# BearJR.net
KiCad netlist of a schematic drawn in EAGLE
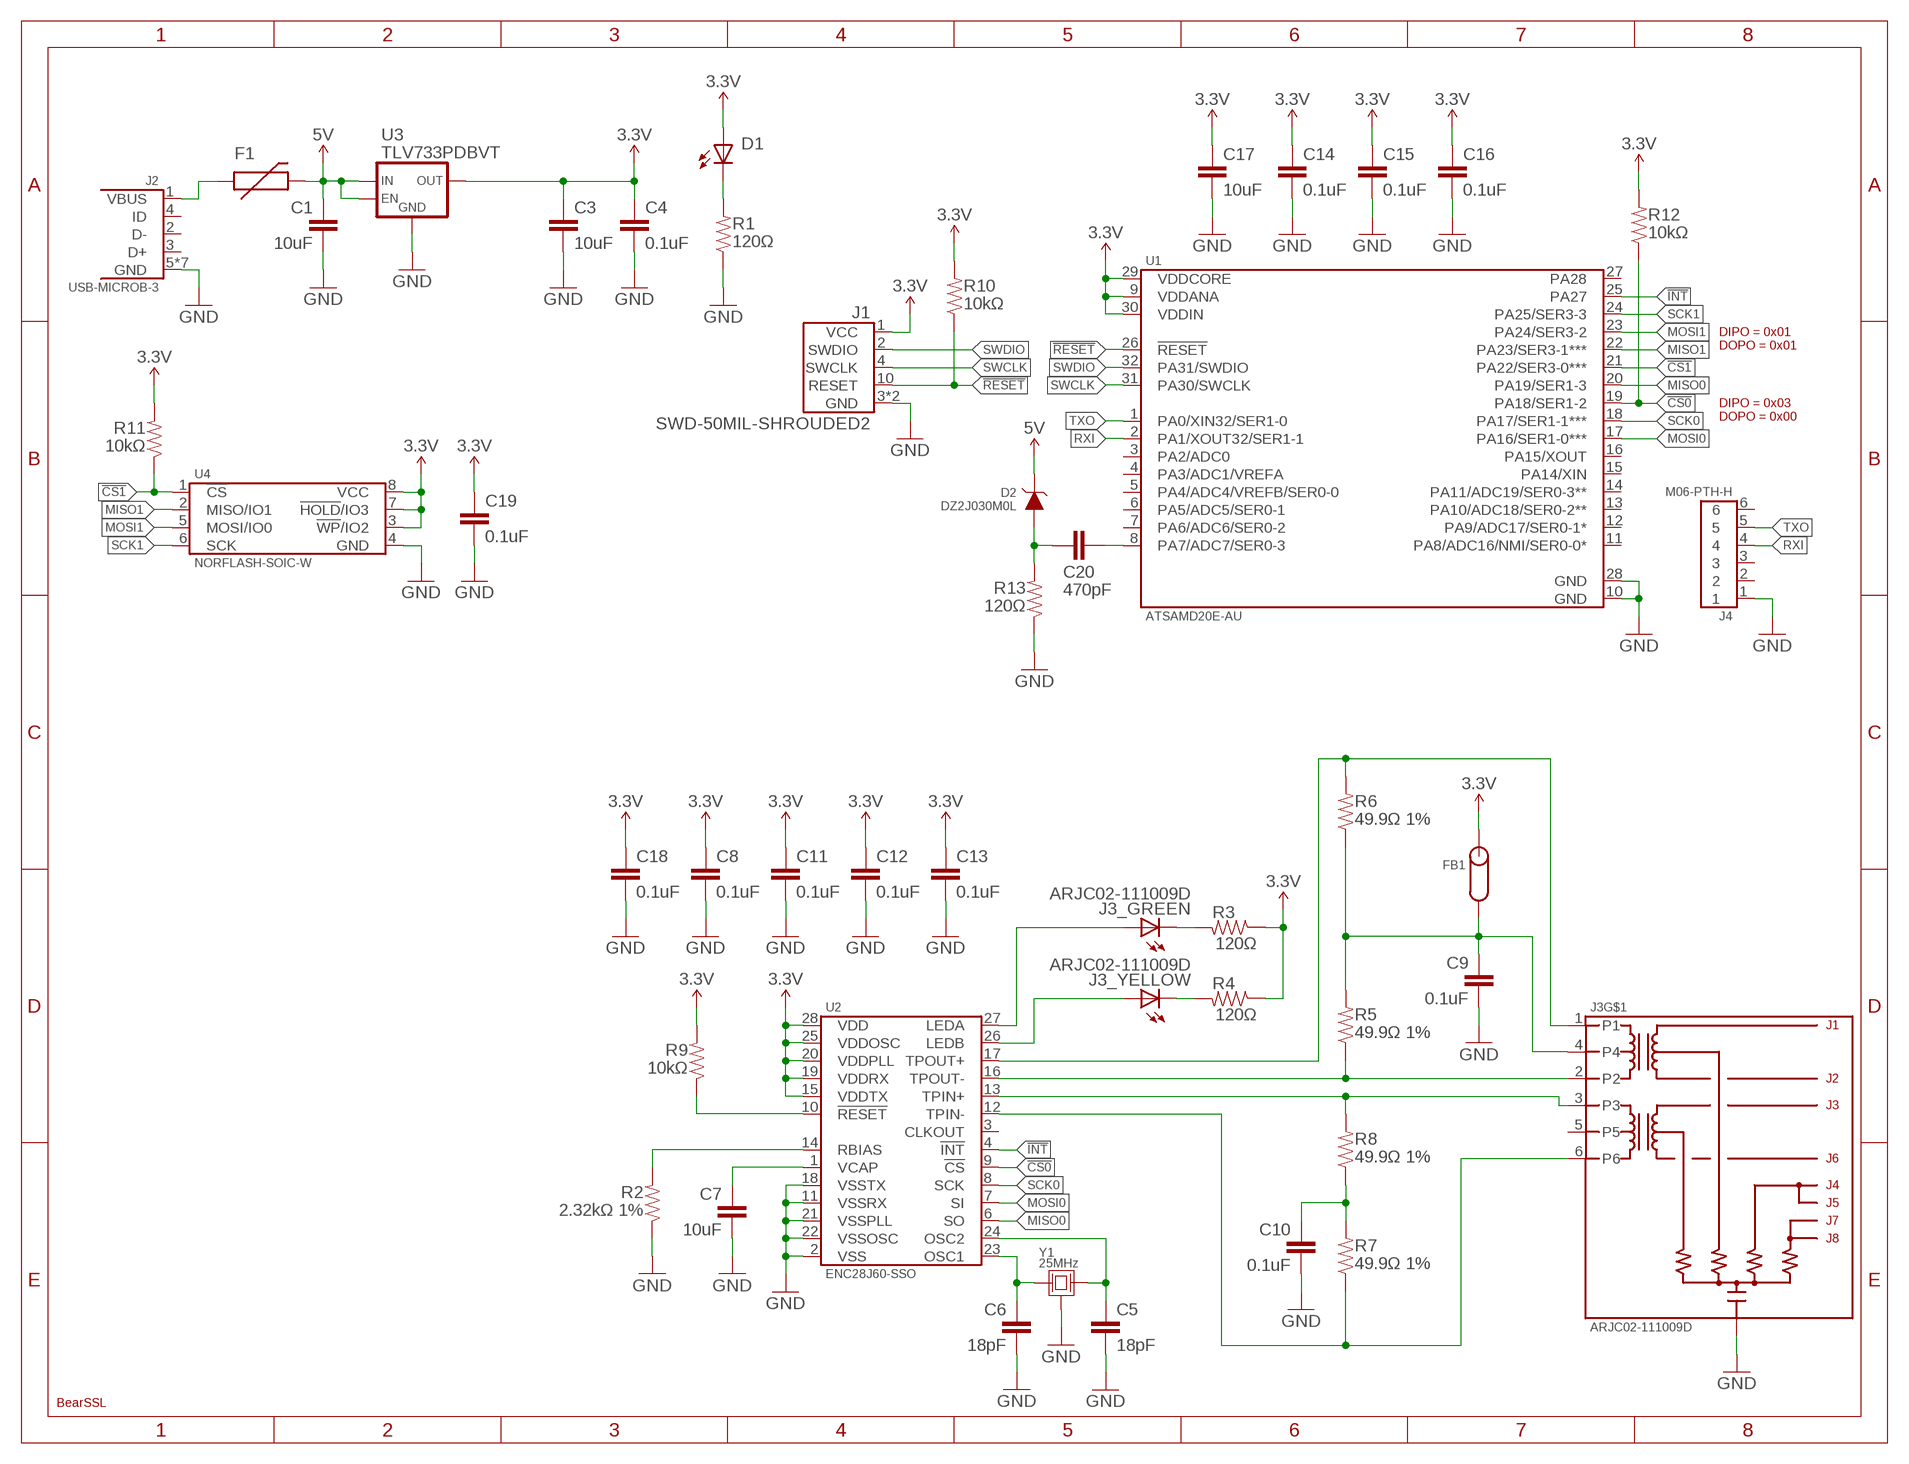
[diagram p0: schematic, sheet 1]

(export (version "E")
  (design (tool "Eeschema 10.0.6"))
  (components
    (comp (ref "C1")
      (value "10uF")
      (footprint "eagle-import:0603-CAP")
      (libsource (lib "eagle-import") (part "CAP-0603"))
    )
    (comp (ref "C3")
      (value "10uF")
      (footprint "eagle-import:0603-CAP")
      (libsource (lib "eagle-import") (part "CAP-0603"))
    )
    (comp (ref "C4")
      (value "0.1uF")
      (footprint "eagle-import:0603-CAP")
      (libsource (lib "eagle-import") (part "CAP-0603"))
    )
    (comp (ref "C5")
      (value "18pF")
      (footprint "eagle-import:0603-CAP")
      (libsource (lib "eagle-import") (part "CAP-0603"))
    )
    (comp (ref "C6")
      (value "18pF")
      (footprint "eagle-import:0603-CAP")
      (libsource (lib "eagle-import") (part "CAP-0603"))
    )
    (comp (ref "C7")
      (value "10uF")
      (footprint "eagle-import:0603-CAP")
      (libsource (lib "eagle-import") (part "CAP-0603"))
    )
    (comp (ref "C8")
      (value "0.1uF")
      (footprint "eagle-import:0603-CAP")
      (libsource (lib "eagle-import") (part "CAP-0603"))
    )
    (comp (ref "C9")
      (value "0.1uF")
      (footprint "eagle-import:0603-CAP")
      (libsource (lib "eagle-import") (part "CAP-0603"))
    )
    (comp (ref "C10")
      (value "0.1uF")
      (footprint "eagle-import:0603-CAP")
      (libsource (lib "eagle-import") (part "CAP-0603"))
    )
    (comp (ref "C11")
      (value "0.1uF")
      (footprint "eagle-import:0603-CAP")
      (libsource (lib "eagle-import") (part "CAP-0603"))
    )
    (comp (ref "C12")
      (value "0.1uF")
      (footprint "eagle-import:0603-CAP")
      (libsource (lib "eagle-import") (part "CAP-0603"))
    )
    (comp (ref "C13")
      (value "0.1uF")
      (footprint "eagle-import:0603-CAP")
      (libsource (lib "eagle-import") (part "CAP-0603"))
    )
    (comp (ref "C14")
      (value "0.1uF")
      (footprint "eagle-import:0603-CAP")
      (libsource (lib "eagle-import") (part "CAP-0603"))
    )
    (comp (ref "C15")
      (value "0.1uF")
      (footprint "eagle-import:0603-CAP")
      (libsource (lib "eagle-import") (part "CAP-0603"))
    )
    (comp (ref "C16")
      (value "0.1uF")
      (footprint "eagle-import:0603-CAP")
      (libsource (lib "eagle-import") (part "CAP-0603"))
    )
    (comp (ref "C17")
      (value "10uF")
      (footprint "eagle-import:0603-CAP")
      (libsource (lib "eagle-import") (part "CAP-0603"))
    )
    (comp (ref "C18")
      (value "0.1uF")
      (footprint "eagle-import:0603-CAP")
      (libsource (lib "eagle-import") (part "CAP-0603"))
    )
    (comp (ref "C19")
      (value "0.1uF")
      (footprint "eagle-import:0603-CAP")
      (libsource (lib "eagle-import") (part "CAP-0603"))
    )
    (comp (ref "C20")
      (value "470pF")
      (footprint "eagle-import:0603-CAP")
      (libsource (lib "eagle-import") (part "CAP-0603"))
    )
    (comp (ref "D1")
      (value "LED-0603")
      (footprint "eagle-import:0603-LED")
      (libsource (lib "eagle-import") (part "LED-0603"))
    )
    (comp (ref "D2")
      (value "DZ2J030M0L")
      (footprint "eagle-import:SC-90")
      (libsource (lib "eagle-import") (part "ZENER-SC90"))
    )
    (comp (ref "F1")
      (value "PTC-1206")
      (footprint "eagle-import:1206-PTC")
      (libsource (lib "eagle-import") (part "PTC-1206"))
    )
    (comp (ref "FB1")
      (value "FERRITE-0805")
      (footprint "eagle-import:0805")
      (libsource (lib "eagle-import") (part "FERRITE-0805"))
    )
    (comp (ref "J1")
      (value "SWD-50MIL-SHROUDED2")
      (footprint "eagle-import:M05X2-50MIL-SHROUD")
      (libsource (lib "eagle-import") (part "SWD-50MIL-SHROUDED2"))
    )
    (comp (ref "J2")
      (value "USB-MICROB-3")
      (footprint "eagle-import:10118192-0001LF")
      (libsource (lib "eagle-import") (part "USB-MICROB-3"))
    )
    (comp (ref "J3")
      (value "ARJC02-111009D")
      (footprint "eagle-import:ETHERNET")
      (libsource (lib "eagle-import") (part "ARJC02-111009D"))
    )
    (comp (ref "J4")
      (value "M06-PTH-H")
      (footprint "eagle-import:M06-PTH-H")
      (libsource (lib "eagle-import") (part "M06-PTH-H"))
    )
    (comp (ref "R1")
      (value "120Ω")
      (footprint "eagle-import:0603-CAP")
      (libsource (lib "eagle-import") (part "RESISTOR-0603"))
    )
    (comp (ref "R2")
      (value "2.32kΩ 1%")
      (footprint "eagle-import:0603-CAP")
      (libsource (lib "eagle-import") (part "RESISTOR-0603"))
    )
    (comp (ref "R3")
      (value "120Ω")
      (footprint "eagle-import:0603-CAP")
      (libsource (lib "eagle-import") (part "RESISTOR-0603"))
    )
    (comp (ref "R4")
      (value "120Ω")
      (footprint "eagle-import:0603-CAP")
      (libsource (lib "eagle-import") (part "RESISTOR-0603"))
    )
    (comp (ref "R5")
      (value "49.9Ω 1%")
      (footprint "eagle-import:0805-RES")
      (libsource (lib "eagle-import") (part "RESISTOR-0805"))
    )
    (comp (ref "R6")
      (value "49.9Ω 1%")
      (footprint "eagle-import:0805-RES")
      (libsource (lib "eagle-import") (part "RESISTOR-0805"))
    )
    (comp (ref "R7")
      (value "49.9Ω 1%")
      (footprint "eagle-import:0805-RES")
      (libsource (lib "eagle-import") (part "RESISTOR-0805"))
    )
    (comp (ref "R8")
      (value "49.9Ω 1%")
      (footprint "eagle-import:0805-RES")
      (libsource (lib "eagle-import") (part "RESISTOR-0805"))
    )
    (comp (ref "R9")
      (value "10kΩ")
      (footprint "eagle-import:0603-CAP")
      (libsource (lib "eagle-import") (part "RESISTOR-0603"))
    )
    (comp (ref "R10")
      (value "10kΩ")
      (footprint "eagle-import:0603-CAP")
      (libsource (lib "eagle-import") (part "RESISTOR-0603"))
    )
    (comp (ref "R11")
      (value "10kΩ")
      (footprint "eagle-import:0603-CAP")
      (libsource (lib "eagle-import") (part "RESISTOR-0603"))
    )
    (comp (ref "R12")
      (value "10kΩ")
      (footprint "eagle-import:0603-CAP")
      (libsource (lib "eagle-import") (part "RESISTOR-0603"))
    )
    (comp (ref "R13")
      (value "120Ω")
      (footprint "eagle-import:0603-CAP")
      (libsource (lib "eagle-import") (part "RESISTOR-0603"))
    )
    (comp (ref "U$1")
      (value "BEAR_SSL")
      (footprint "eagle-import:BEAR_SSL")
      (libsource (lib "eagle-import") (part "BEAR_SSL"))
    )
    (comp (ref "U1")
      (value "ATSAMD20E-AU")
      (footprint "eagle-import:TQFP-32")
      (libsource (lib "eagle-import") (part "ATSAMD20E-AU"))
    )
    (comp (ref "U2")
      (value "ENC28J60-SSO")
      (footprint "eagle-import:SSOP-28")
      (libsource (lib "eagle-import") (part "ENC28J60-SSO"))
    )
    (comp (ref "U3")
      (value "TLV733PDBVT")
      (footprint "eagle-import:SOT-23-5")
      (libsource (lib "eagle-import") (part "TLV733PDBVT"))
    )
    (comp (ref "U4")
      (value "NORFLASH-SOIC-W")
      (footprint "eagle-import:SOIC-8-W")
      (libsource (lib "eagle-import") (part "NORFLASH-SOIC-W"))
    )
    (comp (ref "Y1")
      (value "25MHz")
      (footprint "eagle-import:FA-238")
      (libsource (lib "eagle-import") (part "CRYSTAL-3.2X2.5"))
    )
  )
  (nets
    (net (code "1") (name "/~{CS0}") (class "Default")
      (node (ref "R12") (pin "1") (pinfunction "1_1") (pintype "passive"))
      (node (ref "U1") (pin "19") (pinfunction "PA18/SER1-2_19") (pintype "bidirectional"))
      (node (ref "U2") (pin "9") (pinfunction "~{CS}_9") (pintype "bidirectional"))
    )
    (net (code "2") (name "/~{CS1}") (class "Default")
      (node (ref "R11") (pin "1") (pinfunction "1_1") (pintype "passive"))
      (node (ref "U1") (pin "21") (pinfunction "PA22/SER3-0***_21") (pintype "bidirectional"))
      (node (ref "U4") (pin "1") (pinfunction "~{CS}_1") (pintype "bidirectional"))
    )
    (net (code "3") (name "/~{INT}") (class "Default")
      (node (ref "U1") (pin "25") (pinfunction "PA27_25") (pintype "bidirectional"))
      (node (ref "U2") (pin "4") (pinfunction "~{INT}_4") (pintype "bidirectional"))
    )
    (net (code "4") (name "/~{RESET}") (class "Default")
      (node (ref "J1") (pin "10") (pinfunction "RESET_10") (pintype "bidirectional"))
      (node (ref "R10") (pin "1") (pinfunction "1_1") (pintype "passive"))
      (node (ref "U1") (pin "26") (pinfunction "~{RESET}_26") (pintype "bidirectional"))
    )
    (net (code "5") (name "3.3V") (class "Default")
      (node (ref "C11") (pin "1") (pinfunction "1_1") (pintype "passive"))
      (node (ref "C12") (pin "1") (pinfunction "1_1") (pintype "passive"))
      (node (ref "C13") (pin "1") (pinfunction "1_1") (pintype "passive"))
      (node (ref "C14") (pin "1") (pinfunction "1_1") (pintype "passive"))
      (node (ref "C15") (pin "1") (pinfunction "1_1") (pintype "passive"))
      (node (ref "C16") (pin "1") (pinfunction "1_1") (pintype "passive"))
      (node (ref "C17") (pin "1") (pinfunction "1_1") (pintype "passive"))
      (node (ref "C18") (pin "1") (pinfunction "1_1") (pintype "passive"))
      (node (ref "C19") (pin "1") (pinfunction "1_1") (pintype "passive"))
      (node (ref "C3") (pin "1") (pinfunction "1_1") (pintype "passive"))
      (node (ref "C4") (pin "1") (pinfunction "1_1") (pintype "passive"))
      (node (ref "C8") (pin "1") (pinfunction "1_1") (pintype "passive"))
      (node (ref "D1") (pin "A") (pinfunction "A_A") (pintype "passive"))
      (node (ref "FB1") (pin "2") (pinfunction "P$2_2") (pintype "bidirectional"))
      (node (ref "J1") (pin "1") (pinfunction "VCC_1") (pintype "bidirectional"))
      (node (ref "R10") (pin "2") (pinfunction "2_2") (pintype "passive"))
      (node (ref "R11") (pin "2") (pinfunction "2_2") (pintype "passive"))
      (node (ref "R12") (pin "2") (pinfunction "2_2") (pintype "passive"))
      (node (ref "R3") (pin "1") (pinfunction "1_1") (pintype "passive"))
      (node (ref "R4") (pin "1") (pinfunction "1_1") (pintype "passive"))
      (node (ref "R9") (pin "2") (pinfunction "2_2") (pintype "passive"))
      (node (ref "U1") (pin "29") (pinfunction "VDDCORE_29") (pintype "bidirectional"))
      (node (ref "U1") (pin "30") (pinfunction "VDDIN_30") (pintype "bidirectional"))
      (node (ref "U1") (pin "9") (pinfunction "VDDANA_9") (pintype "bidirectional"))
      (node (ref "U2") (pin "15") (pinfunction "VDDTX_15") (pintype "bidirectional"))
      (node (ref "U2") (pin "19") (pinfunction "VDDRX_19") (pintype "bidirectional"))
      (node (ref "U2") (pin "20") (pinfunction "VDDPLL_20") (pintype "bidirectional"))
      (node (ref "U2") (pin "25") (pinfunction "VDDOSC_25") (pintype "bidirectional"))
      (node (ref "U2") (pin "28") (pinfunction "VDD_28") (pintype "bidirectional"))
      (node (ref "U3") (pin "5") (pinfunction "OUT_5") (pintype "output"))
      (node (ref "U4") (pin "3") (pinfunction "~{WP}/IO2_3") (pintype "bidirectional"))
      (node (ref "U4") (pin "7") (pinfunction "~{HOLD}/IO3_7") (pintype "bidirectional"))
      (node (ref "U4") (pin "8") (pinfunction "VCC_8") (pintype "bidirectional"))
    )
    (net (code "6") (name "5V") (class "Default")
      (node (ref "C1") (pin "1") (pinfunction "1_1") (pintype "passive"))
      (node (ref "D2") (pin "C") (pinfunction "C_C") (pintype "bidirectional"))
      (node (ref "F1") (pin "P$2") (pinfunction "2_P$2") (pintype "bidirectional"))
      (node (ref "U3") (pin "1") (pinfunction "IN_1") (pintype "input"))
      (node (ref "U3") (pin "3") (pinfunction "EN_3") (pintype "input"))
    )
    (net (code "7") (name "GND") (class "Default")
      (node (ref "C1") (pin "2") (pinfunction "2_2") (pintype "passive"))
      (node (ref "C10") (pin "2") (pinfunction "2_2") (pintype "passive"))
      (node (ref "C11") (pin "2") (pinfunction "2_2") (pintype "passive"))
      (node (ref "C12") (pin "2") (pinfunction "2_2") (pintype "passive"))
      (node (ref "C13") (pin "2") (pinfunction "2_2") (pintype "passive"))
      (node (ref "C14") (pin "2") (pinfunction "2_2") (pintype "passive"))
      (node (ref "C15") (pin "2") (pinfunction "2_2") (pintype "passive"))
      (node (ref "C16") (pin "2") (pinfunction "2_2") (pintype "passive"))
      (node (ref "C17") (pin "2") (pinfunction "2_2") (pintype "passive"))
      (node (ref "C18") (pin "2") (pinfunction "2_2") (pintype "passive"))
      (node (ref "C19") (pin "2") (pinfunction "2_2") (pintype "passive"))
      (node (ref "C3") (pin "2") (pinfunction "2_2") (pintype "passive"))
      (node (ref "C4") (pin "2") (pinfunction "2_2") (pintype "passive"))
      (node (ref "C5") (pin "2") (pinfunction "2_2") (pintype "passive"))
      (node (ref "C6") (pin "2") (pinfunction "2_2") (pintype "passive"))
      (node (ref "C7") (pin "2") (pinfunction "2_2") (pintype "passive"))
      (node (ref "C8") (pin "2") (pinfunction "2_2") (pintype "passive"))
      (node (ref "C9") (pin "2") (pinfunction "2_2") (pintype "passive"))
      (node (ref "J1") (pin "3") (pinfunction "GND_3") (pintype "bidirectional"))
      (node (ref "J1") (pin "5") (pinfunction "GND_5") (pintype "bidirectional"))
      (node (ref "J2") (pin "5") (pinfunction "GND_5") (pintype "bidirectional"))
      (node (ref "J2") (pin "P$10") (pinfunction "GND_P$10") (pintype "bidirectional"))
      (node (ref "J2") (pin "P$11") (pinfunction "GND_P$11") (pintype "bidirectional"))
      (node (ref "J2") (pin "P$6") (pinfunction "GND_P$6") (pintype "bidirectional"))
      (node (ref "J2") (pin "P$7") (pinfunction "GND_P$7") (pintype "bidirectional"))
      (node (ref "J2") (pin "P$8") (pinfunction "GND_P$8") (pintype "bidirectional"))
      (node (ref "J2") (pin "P$9") (pinfunction "GND_P$9") (pintype "bidirectional"))
      (node (ref "J3") (pin "8") (pinfunction "P8_8") (pintype "bidirectional"))
      (node (ref "J3") (pin "P$5") (pinfunction "P8_P$5") (pintype "bidirectional"))
      (node (ref "J3") (pin "P$6") (pinfunction "P8_P$6") (pintype "bidirectional"))
      (node (ref "J4") (pin "1") (pinfunction "1_1") (pintype "bidirectional"))
      (node (ref "R1") (pin "1") (pinfunction "1_1") (pintype "passive"))
      (node (ref "R13") (pin "1") (pinfunction "1_1") (pintype "passive"))
      (node (ref "R2") (pin "1") (pinfunction "1_1") (pintype "passive"))
      (node (ref "U1") (pin "10") (pinfunction "GND_10") (pintype "bidirectional"))
      (node (ref "U1") (pin "28") (pinfunction "GND_28") (pintype "bidirectional"))
      (node (ref "U2") (pin "11") (pinfunction "VSSRX_11") (pintype "bidirectional"))
      (node (ref "U2") (pin "18") (pinfunction "VSSTX_18") (pintype "bidirectional"))
      (node (ref "U2") (pin "2") (pinfunction "VSS_2") (pintype "bidirectional"))
      (node (ref "U2") (pin "21") (pinfunction "VSSPLL_21") (pintype "bidirectional"))
      (node (ref "U2") (pin "22") (pinfunction "VSSOSC_22") (pintype "bidirectional"))
      (node (ref "U3") (pin "2") (pinfunction "GND_2") (pintype "input"))
      (node (ref "U4") (pin "4") (pinfunction "GND_4") (pintype "bidirectional"))
      (node (ref "Y1") (pin "2") (pinfunction "GND_2") (pintype "bidirectional"))
      (node (ref "Y1") (pin "4") (pinfunction "GND_4") (pintype "bidirectional"))
    )
    (net (code "8") (name "MISO0") (class "Default")
      (node (ref "U1") (pin "20") (pinfunction "PA19/SER1-3_20") (pintype "bidirectional"))
      (node (ref "U2") (pin "6") (pinfunction "SO_6") (pintype "bidirectional"))
    )
    (net (code "9") (name "MISO1") (class "Default")
      (node (ref "U1") (pin "22") (pinfunction "PA23/SER3-1***_22") (pintype "bidirectional"))
      (node (ref "U4") (pin "2") (pinfunction "MISO/IO1_2") (pintype "bidirectional"))
    )
    (net (code "10") (name "MOSI0") (class "Default")
      (node (ref "U1") (pin "17") (pinfunction "PA16/SER1-0***_17") (pintype "bidirectional"))
      (node (ref "U2") (pin "7") (pinfunction "SI_7") (pintype "bidirectional"))
    )
    (net (code "11") (name "MOSI1") (class "Default")
      (node (ref "U1") (pin "23") (pinfunction "PA24/SER3-2_23") (pintype "bidirectional"))
      (node (ref "U4") (pin "5") (pinfunction "MOSI/IO0_5") (pintype "bidirectional"))
    )
    (net (code "12") (name "Net-(C10-Pad1)") (class "Default")
      (node (ref "C10") (pin "1") (pinfunction "1_1") (pintype "passive"))
      (node (ref "R7") (pin "2") (pinfunction "2_2") (pintype "passive"))
      (node (ref "R8") (pin "1") (pinfunction "1_1") (pintype "passive"))
    )
    (net (code "13") (name "Net-(C20-Pad1)") (class "Default")
      (node (ref "C20") (pin "1") (pinfunction "1_1") (pintype "passive"))
      (node (ref "D2") (pin "A") (pinfunction "A_A") (pintype "bidirectional"))
      (node (ref "R13") (pin "2") (pinfunction "2_2") (pintype "passive"))
    )
    (net (code "14") (name "Net-(D1-PadC)") (class "Default")
      (node (ref "D1") (pin "C") (pinfunction "C_C") (pintype "passive"))
      (node (ref "R1") (pin "2") (pinfunction "2_2") (pintype "passive"))
    )
    (net (code "15") (name "Net-(F1-1)") (class "Default")
      (node (ref "F1") (pin "P$1") (pinfunction "1_P$1") (pintype "bidirectional"))
      (node (ref "J2") (pin "1") (pinfunction "VBUS_1") (pintype "bidirectional"))
    )
    (net (code "16") (name "Net-(FB1-P$1)") (class "Default")
      (node (ref "C9") (pin "1") (pinfunction "1_1") (pintype "passive"))
      (node (ref "FB1") (pin "1") (pinfunction "P$1_1") (pintype "bidirectional"))
      (node (ref "J3") (pin "4") (pinfunction "P4_4") (pintype "bidirectional"))
      (node (ref "R5") (pin "2") (pinfunction "2_2") (pintype "passive"))
      (node (ref "R6") (pin "1") (pinfunction "1_1") (pintype "passive"))
    )
    (net (code "17") (name "Net-(J3A-P1)") (class "Default")
      (node (ref "J3") (pin "1") (pinfunction "P1_1") (pintype "bidirectional"))
      (node (ref "R6") (pin "2") (pinfunction "2_2") (pintype "passive"))
      (node (ref "U2") (pin "17") (pinfunction "TPOUT+_17") (pintype "bidirectional"))
    )
    (net (code "18") (name "Net-(J3A-P2)") (class "Default")
      (node (ref "J3") (pin "2") (pinfunction "P2_2") (pintype "bidirectional"))
      (node (ref "R5") (pin "1") (pinfunction "1_1") (pintype "passive"))
      (node (ref "U2") (pin "16") (pinfunction "TPOUT-_16") (pintype "bidirectional"))
    )
    (net (code "19") (name "Net-(J3A-P3)") (class "Default")
      (node (ref "J3") (pin "3") (pinfunction "P3_3") (pintype "bidirectional"))
      (node (ref "R8") (pin "2") (pinfunction "2_2") (pintype "passive"))
      (node (ref "U2") (pin "13") (pinfunction "TPIN+_13") (pintype "bidirectional"))
    )
    (net (code "20") (name "Net-(J3A-P6)") (class "Default")
      (node (ref "J3") (pin "6") (pinfunction "P6_6") (pintype "bidirectional"))
      (node (ref "R7") (pin "1") (pinfunction "1_1") (pintype "passive"))
      (node (ref "U2") (pin "12") (pinfunction "TPIN-_12") (pintype "bidirectional"))
    )
    (net (code "21") (name "Net-(J3B-A)") (class "Default")
      (node (ref "J3") (pin "9") (pinfunction "A_9") (pintype "passive"))
      (node (ref "U2") (pin "27") (pinfunction "LEDA_27") (pintype "bidirectional"))
    )
    (net (code "22") (name "Net-(J3B-C)") (class "Default")
      (node (ref "J3") (pin "10") (pinfunction "C_10") (pintype "passive"))
      (node (ref "R3") (pin "2") (pinfunction "2_2") (pintype "passive"))
    )
    (net (code "23") (name "Net-(J3C-A)") (class "Default")
      (node (ref "J3") (pin "11") (pinfunction "A_11") (pintype "passive"))
      (node (ref "U2") (pin "26") (pinfunction "LEDB_26") (pintype "bidirectional"))
    )
    (net (code "24") (name "Net-(J3C-C)") (class "Default")
      (node (ref "J3") (pin "12") (pinfunction "C_12") (pintype "passive"))
      (node (ref "R4") (pin "2") (pinfunction "2_2") (pintype "passive"))
    )
    (net (code "25") (name "Net-(U1-PA7{slash}ADC7{slash}SER0-3)") (class "Default")
      (node (ref "C20") (pin "2") (pinfunction "2_2") (pintype "passive"))
      (node (ref "U1") (pin "8") (pinfunction "PA7/ADC7/SER0-3_8") (pintype "bidirectional"))
    )
    (net (code "26") (name "Net-(U2-OSC1)") (class "Default")
      (node (ref "C6") (pin "1") (pinfunction "1_1") (pintype "passive"))
      (node (ref "U2") (pin "23") (pinfunction "OSC1_23") (pintype "bidirectional"))
      (node (ref "Y1") (pin "1") (pinfunction "1_1") (pintype "bidirectional"))
    )
    (net (code "27") (name "Net-(U2-OSC2)") (class "Default")
      (node (ref "C5") (pin "1") (pinfunction "1_1") (pintype "passive"))
      (node (ref "U2") (pin "24") (pinfunction "OSC2_24") (pintype "bidirectional"))
      (node (ref "Y1") (pin "3") (pinfunction "2_3") (pintype "bidirectional"))
    )
    (net (code "28") (name "Net-(U2-RBIAS)") (class "Default")
      (node (ref "R2") (pin "2") (pinfunction "2_2") (pintype "passive"))
      (node (ref "U2") (pin "14") (pinfunction "RBIAS_14") (pintype "bidirectional"))
    )
    (net (code "29") (name "Net-(U2-VCAP)") (class "Default")
      (node (ref "C7") (pin "1") (pinfunction "1_1") (pintype "passive"))
      (node (ref "U2") (pin "1") (pinfunction "VCAP_1") (pintype "bidirectional"))
    )
    (net (code "30") (name "Net-(U2-~{RESET})") (class "Default")
      (node (ref "R9") (pin "1") (pinfunction "1_1") (pintype "passive"))
      (node (ref "U2") (pin "10") (pinfunction "~{RESET}_10") (pintype "bidirectional"))
    )
    (net (code "31") (name "RXI") (class "Default")
      (node (ref "J4") (pin "4") (pinfunction "4_4") (pintype "bidirectional"))
      (node (ref "U1") (pin "2") (pinfunction "PA1/XOUT32/SER1-1_2") (pintype "bidirectional"))
    )
    (net (code "32") (name "SCK0") (class "Default")
      (node (ref "U1") (pin "18") (pinfunction "PA17/SER1-1***_18") (pintype "bidirectional"))
      (node (ref "U2") (pin "8") (pinfunction "SCK_8") (pintype "bidirectional"))
    )
    (net (code "33") (name "SCK1") (class "Default")
      (node (ref "U1") (pin "24") (pinfunction "PA25/SER3-3_24") (pintype "bidirectional"))
      (node (ref "U4") (pin "6") (pinfunction "SCK_6") (pintype "bidirectional"))
    )
    (net (code "34") (name "SWCLK") (class "Default")
      (node (ref "J1") (pin "4") (pinfunction "SWCLK_4") (pintype "bidirectional"))
      (node (ref "U1") (pin "31") (pinfunction "PA30/SWCLK_31") (pintype "bidirectional"))
    )
    (net (code "35") (name "SWDIO") (class "Default")
      (node (ref "J1") (pin "2") (pinfunction "SWDIO_2") (pintype "bidirectional"))
      (node (ref "U1") (pin "32") (pinfunction "PA31/SWDIO_32") (pintype "bidirectional"))
    )
    (net (code "36") (name "TXO") (class "Default")
      (node (ref "J4") (pin "5") (pinfunction "5_5") (pintype "bidirectional"))
      (node (ref "U1") (pin "1") (pinfunction "PA0/XIN32/SER1-0_1") (pintype "bidirectional"))
    )
    (net (code "37") (name "unconnected-(J2-D+-Pad3)") (class "Default")
      (node (ref "J2") (pin "3") (pinfunction "D+_3") (pintype "bidirectional"))
    )
    (net (code "38") (name "unconnected-(J2-D--Pad2)") (class "Default")
      (node (ref "J2") (pin "2") (pinfunction "D-_2") (pintype "bidirectional"))
    )
    (net (code "39") (name "unconnected-(J2-ID-Pad4)") (class "Default")
      (node (ref "J2") (pin "4") (pinfunction "ID_4") (pintype "bidirectional"))
    )
    (net (code "40") (name "unconnected-(J3A-P5-Pad5)") (class "Default")
      (node (ref "J3") (pin "5") (pinfunction "P5_5") (pintype "bidirectional"))
    )
    (net (code "41") (name "unconnected-(J4-Pad2)") (class "Default")
      (node (ref "J4") (pin "2") (pinfunction "2_2") (pintype "bidirectional"))
    )
    (net (code "42") (name "unconnected-(J4-Pad3)") (class "Default")
      (node (ref "J4") (pin "3") (pinfunction "3_3") (pintype "bidirectional"))
    )
    (net (code "43") (name "unconnected-(J4-Pad6)") (class "Default")
      (node (ref "J4") (pin "6") (pinfunction "6_6") (pintype "bidirectional"))
    )
    (net (code "44") (name "unconnected-(U1-PA2{slash}ADC0-Pad3)") (class "Default")
      (node (ref "U1") (pin "3") (pinfunction "PA2/ADC0_3") (pintype "bidirectional"))
    )
    (net (code "45") (name "unconnected-(U1-PA3{slash}ADC1{slash}VREFA-Pad4)") (class "Default")
      (node (ref "U1") (pin "4") (pinfunction "PA3/ADC1/VREFA_4") (pintype "bidirectional"))
    )
    (net (code "46") (name "unconnected-(U1-PA4{slash}ADC4{slash}VREFB{slash}SER0-0-Pad5)") (class "Default")
      (node (ref "U1") (pin "5") (pinfunction "PA4/ADC4/VREFB/SER0-0_5") (pintype "bidirectional"))
    )
    (net (code "47") (name "unconnected-(U1-PA5{slash}ADC5{slash}SER0-1-Pad6)") (class "Default")
      (node (ref "U1") (pin "6") (pinfunction "PA5/ADC5/SER0-1_6") (pintype "bidirectional"))
    )
    (net (code "48") (name "unconnected-(U1-PA6{slash}ADC6{slash}SER0-2-Pad7)") (class "Default")
      (node (ref "U1") (pin "7") (pinfunction "PA6/ADC6/SER0-2_7") (pintype "bidirectional"))
    )
    (net (code "49") (name "unconnected-(U1-PA8{slash}ADC16{slash}NMI{slash}SER0-0*-Pad11)") (class "Default")
      (node (ref "U1") (pin "11") (pinfunction "PA8/ADC16/NMI/SER0-0*_11") (pintype "bidirectional"))
    )
    (net (code "50") (name "unconnected-(U1-PA9{slash}ADC17{slash}SER0-1*-Pad12)") (class "Default")
      (node (ref "U1") (pin "12") (pinfunction "PA9/ADC17/SER0-1*_12") (pintype "bidirectional"))
    )
    (net (code "51") (name "unconnected-(U1-PA10{slash}ADC18{slash}SER0-2**-Pad13)") (class "Default")
      (node (ref "U1") (pin "13") (pinfunction "PA10/ADC18/SER0-2**_13") (pintype "bidirectional"))
    )
    (net (code "52") (name "unconnected-(U1-PA11{slash}ADC19{slash}SER0-3**-Pad14)") (class "Default")
      (node (ref "U1") (pin "14") (pinfunction "PA11/ADC19/SER0-3**_14") (pintype "bidirectional"))
    )
    (net (code "53") (name "unconnected-(U1-PA14{slash}XIN-Pad15)") (class "Default")
      (node (ref "U1") (pin "15") (pinfunction "PA14/XIN_15") (pintype "bidirectional"))
    )
    (net (code "54") (name "unconnected-(U1-PA15{slash}XOUT-Pad16)") (class "Default")
      (node (ref "U1") (pin "16") (pinfunction "PA15/XOUT_16") (pintype "bidirectional"))
    )
    (net (code "55") (name "unconnected-(U1-PA28-Pad27)") (class "Default")
      (node (ref "U1") (pin "27") (pinfunction "PA28_27") (pintype "bidirectional"))
    )
    (net (code "56") (name "unconnected-(U2-CLKOUT-Pad3)") (class "Default")
      (node (ref "U2") (pin "3") (pinfunction "CLKOUT_3") (pintype "bidirectional"))
    )
  )
)
